# M051X.net
KiCad netlist of a schematic drawn in EAGLE
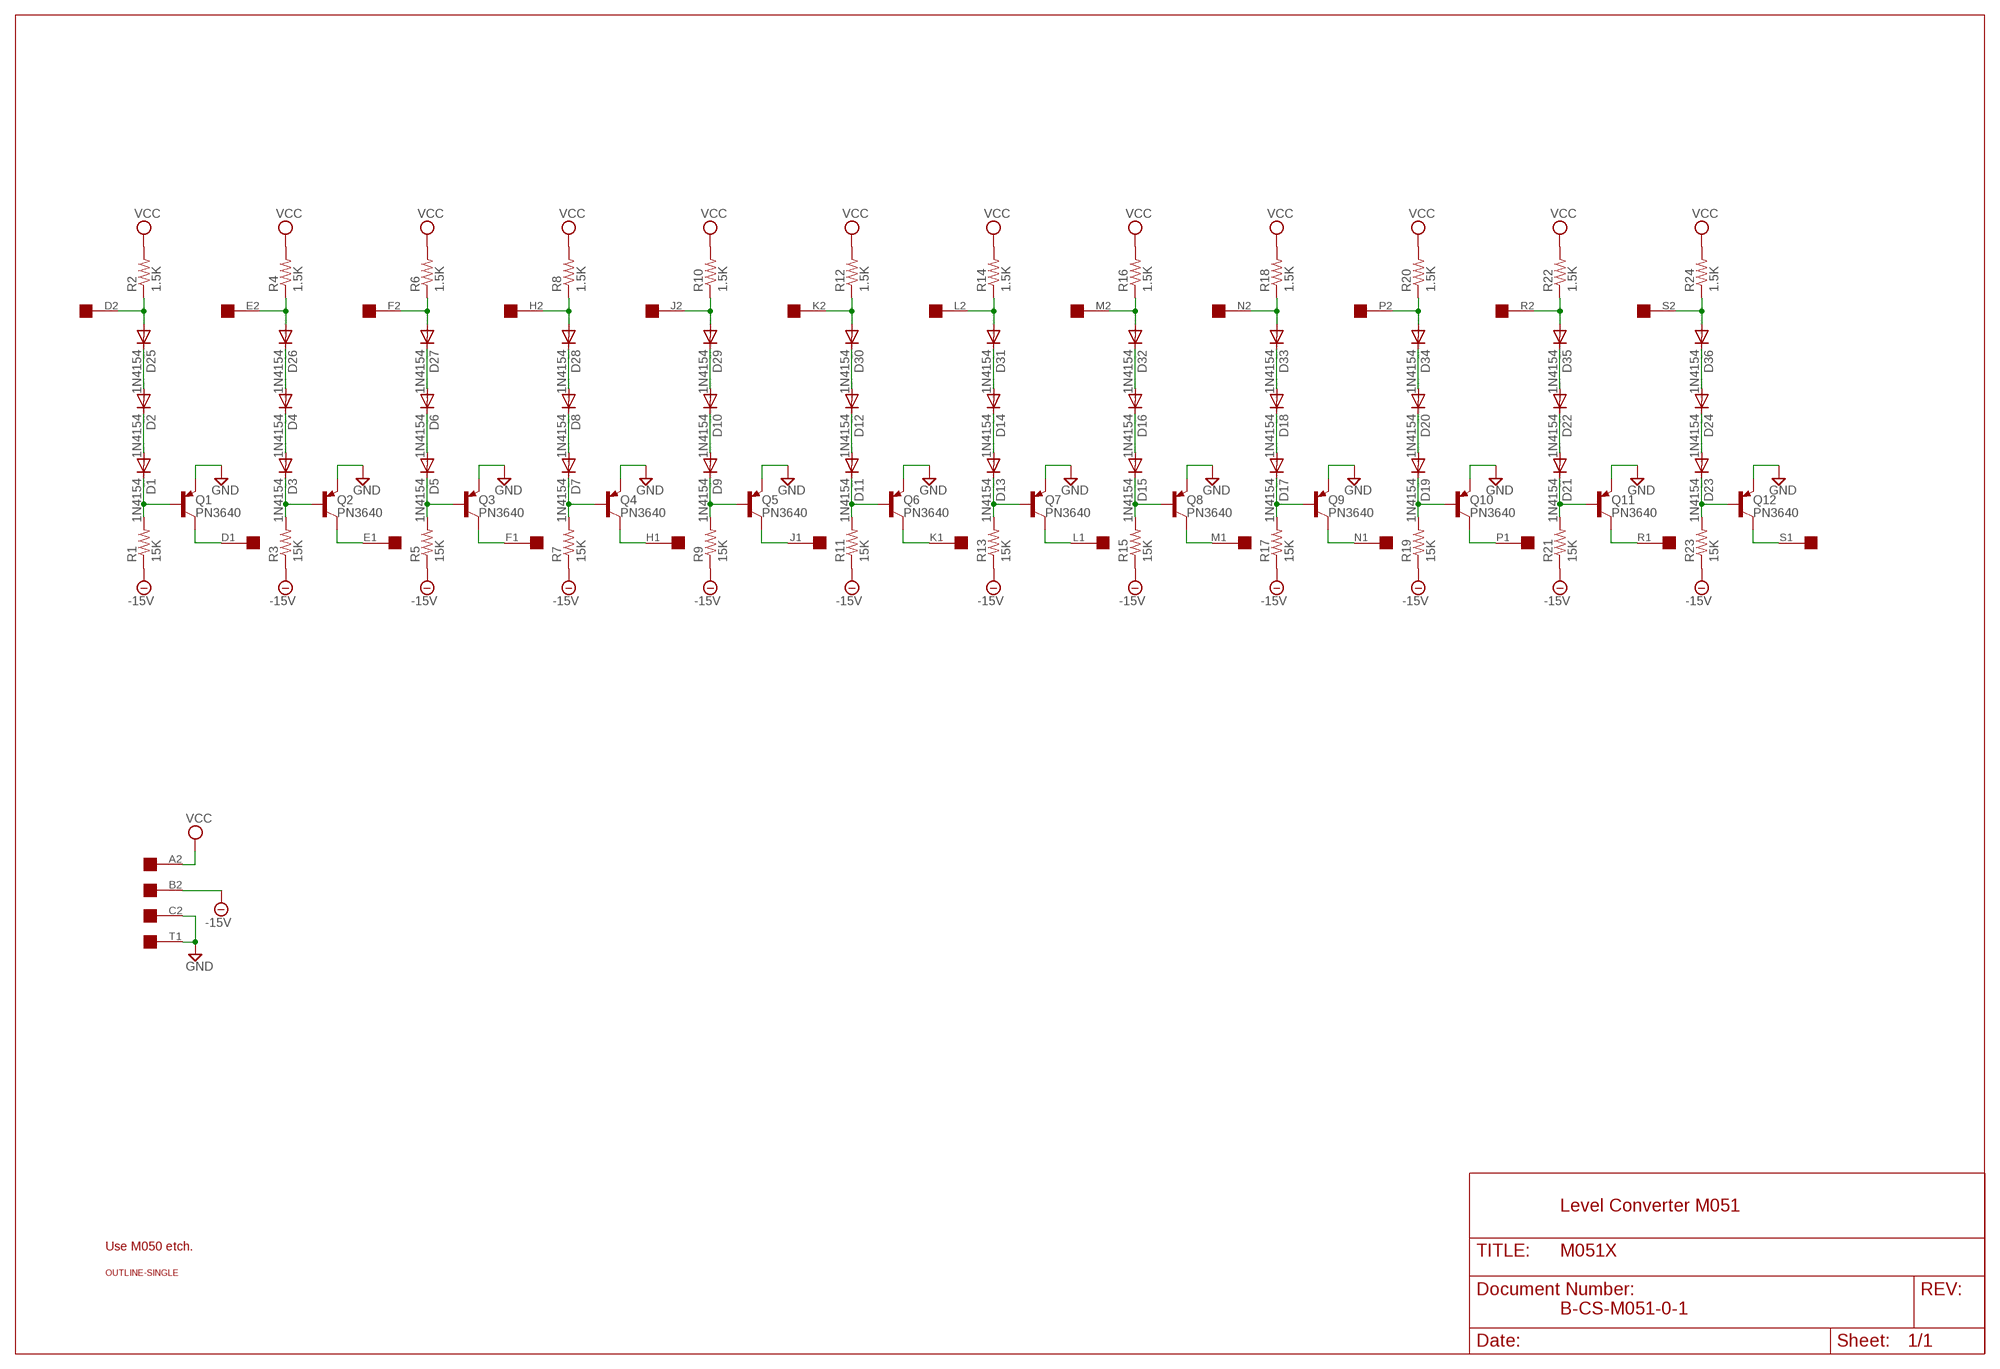
[diagram p0: schematic, sheet 1]

(export (version "E")
  (design (tool "Eeschema 10.0.6"))
  (components
    (comp (ref "D1")
      (value "1N4154")
      (footprint "eagle-import:DO35-10")
      (libsource (lib "eagle-import") (part "DIODE-DO35-10"))
    )
    (comp (ref "D2")
      (value "1N4154")
      (footprint "eagle-import:DO35-10")
      (libsource (lib "eagle-import") (part "DIODE-DO35-10"))
    )
    (comp (ref "D3")
      (value "1N4154")
      (footprint "eagle-import:DO35-10")
      (libsource (lib "eagle-import") (part "DIODE-DO35-10"))
    )
    (comp (ref "D4")
      (value "1N4154")
      (footprint "eagle-import:DO35-10")
      (libsource (lib "eagle-import") (part "DIODE-DO35-10"))
    )
    (comp (ref "D5")
      (value "1N4154")
      (footprint "eagle-import:DO35-10")
      (libsource (lib "eagle-import") (part "DIODE-DO35-10"))
    )
    (comp (ref "D6")
      (value "1N4154")
      (footprint "eagle-import:DO35-10")
      (libsource (lib "eagle-import") (part "DIODE-DO35-10"))
    )
    (comp (ref "D7")
      (value "1N4154")
      (footprint "eagle-import:DO35-10")
      (libsource (lib "eagle-import") (part "DIODE-DO35-10"))
    )
    (comp (ref "D8")
      (value "1N4154")
      (footprint "eagle-import:DO35-10")
      (libsource (lib "eagle-import") (part "DIODE-DO35-10"))
    )
    (comp (ref "D9")
      (value "1N4154")
      (footprint "eagle-import:DO35-10")
      (libsource (lib "eagle-import") (part "DIODE-DO35-10"))
    )
    (comp (ref "D10")
      (value "1N4154")
      (footprint "eagle-import:DO35-10")
      (libsource (lib "eagle-import") (part "DIODE-DO35-10"))
    )
    (comp (ref "D11")
      (value "1N4154")
      (footprint "eagle-import:DO35-10")
      (libsource (lib "eagle-import") (part "DIODE-DO35-10"))
    )
    (comp (ref "D12")
      (value "1N4154")
      (footprint "eagle-import:DO35-10")
      (libsource (lib "eagle-import") (part "DIODE-DO35-10"))
    )
    (comp (ref "D13")
      (value "1N4154")
      (footprint "eagle-import:DO35-10")
      (libsource (lib "eagle-import") (part "DIODE-DO35-10"))
    )
    (comp (ref "D14")
      (value "1N4154")
      (footprint "eagle-import:DO35-10")
      (libsource (lib "eagle-import") (part "DIODE-DO35-10"))
    )
    (comp (ref "D15")
      (value "1N4154")
      (footprint "eagle-import:DO35-10")
      (libsource (lib "eagle-import") (part "DIODE-DO35-10"))
    )
    (comp (ref "D16")
      (value "1N4154")
      (footprint "eagle-import:DO35-10")
      (libsource (lib "eagle-import") (part "DIODE-DO35-10"))
    )
    (comp (ref "D17")
      (value "1N4154")
      (footprint "eagle-import:DO35-10")
      (libsource (lib "eagle-import") (part "DIODE-DO35-10"))
    )
    (comp (ref "D18")
      (value "1N4154")
      (footprint "eagle-import:DO35-10")
      (libsource (lib "eagle-import") (part "DIODE-DO35-10"))
    )
    (comp (ref "D19")
      (value "1N4154")
      (footprint "eagle-import:DO35-10")
      (libsource (lib "eagle-import") (part "DIODE-DO35-10"))
    )
    (comp (ref "D20")
      (value "1N4154")
      (footprint "eagle-import:DO35-10")
      (libsource (lib "eagle-import") (part "DIODE-DO35-10"))
    )
    (comp (ref "D21")
      (value "1N4154")
      (footprint "eagle-import:DO35-10")
      (libsource (lib "eagle-import") (part "DIODE-DO35-10"))
    )
    (comp (ref "D22")
      (value "1N4154")
      (footprint "eagle-import:DO35-10")
      (libsource (lib "eagle-import") (part "DIODE-DO35-10"))
    )
    (comp (ref "D23")
      (value "1N4154")
      (footprint "eagle-import:DO35-10")
      (libsource (lib "eagle-import") (part "DIODE-DO35-10"))
    )
    (comp (ref "D24")
      (value "1N4154")
      (footprint "eagle-import:DO35-10")
      (libsource (lib "eagle-import") (part "DIODE-DO35-10"))
    )
    (comp (ref "D25")
      (value "1N4154")
      (footprint "eagle-import:DO35-10")
      (libsource (lib "eagle-import") (part "DIODE-DO35-10"))
    )
    (comp (ref "D26")
      (value "1N4154")
      (footprint "eagle-import:DO35-10")
      (libsource (lib "eagle-import") (part "DIODE-DO35-10"))
    )
    (comp (ref "D27")
      (value "1N4154")
      (footprint "eagle-import:DO35-10")
      (libsource (lib "eagle-import") (part "DIODE-DO35-10"))
    )
    (comp (ref "D28")
      (value "1N4154")
      (footprint "eagle-import:DO35-10")
      (libsource (lib "eagle-import") (part "DIODE-DO35-10"))
    )
    (comp (ref "D29")
      (value "1N4154")
      (footprint "eagle-import:DO35-10")
      (libsource (lib "eagle-import") (part "DIODE-DO35-10"))
    )
    (comp (ref "D30")
      (value "1N4154")
      (footprint "eagle-import:DO35-10")
      (libsource (lib "eagle-import") (part "DIODE-DO35-10"))
    )
    (comp (ref "D31")
      (value "1N4154")
      (footprint "eagle-import:DO35-10")
      (libsource (lib "eagle-import") (part "DIODE-DO35-10"))
    )
    (comp (ref "D32")
      (value "1N4154")
      (footprint "eagle-import:DO35-10")
      (libsource (lib "eagle-import") (part "DIODE-DO35-10"))
    )
    (comp (ref "D33")
      (value "1N4154")
      (footprint "eagle-import:DO35-10")
      (libsource (lib "eagle-import") (part "DIODE-DO35-10"))
    )
    (comp (ref "D34")
      (value "1N4154")
      (footprint "eagle-import:DO35-10")
      (libsource (lib "eagle-import") (part "DIODE-DO35-10"))
    )
    (comp (ref "D35")
      (value "1N4154")
      (footprint "eagle-import:DO35-10")
      (libsource (lib "eagle-import") (part "DIODE-DO35-10"))
    )
    (comp (ref "D36")
      (value "1N4154")
      (footprint "eagle-import:DO35-10")
      (libsource (lib "eagle-import") (part "DIODE-DO35-10"))
    )
    (comp (ref "Q1")
      (value "PN3640")
      (footprint "eagle-import:TO5")
      (libsource (lib "eagle-import") (part "-PNP-TO5"))
    )
    (comp (ref "Q2")
      (value "PN3640")
      (footprint "eagle-import:TO5")
      (libsource (lib "eagle-import") (part "-PNP-TO5"))
    )
    (comp (ref "Q3")
      (value "PN3640")
      (footprint "eagle-import:TO5")
      (libsource (lib "eagle-import") (part "-PNP-TO5"))
    )
    (comp (ref "Q4")
      (value "PN3640")
      (footprint "eagle-import:TO5")
      (libsource (lib "eagle-import") (part "-PNP-TO5"))
    )
    (comp (ref "Q5")
      (value "PN3640")
      (footprint "eagle-import:TO5")
      (libsource (lib "eagle-import") (part "-PNP-TO5"))
    )
    (comp (ref "Q6")
      (value "PN3640")
      (footprint "eagle-import:TO5")
      (libsource (lib "eagle-import") (part "-PNP-TO5"))
    )
    (comp (ref "Q7")
      (value "PN3640")
      (footprint "eagle-import:TO5")
      (libsource (lib "eagle-import") (part "-PNP-TO5"))
    )
    (comp (ref "Q8")
      (value "PN3640")
      (footprint "eagle-import:TO5")
      (libsource (lib "eagle-import") (part "-PNP-TO5"))
    )
    (comp (ref "Q9")
      (value "PN3640")
      (footprint "eagle-import:TO5")
      (libsource (lib "eagle-import") (part "-PNP-TO5"))
    )
    (comp (ref "Q10")
      (value "PN3640")
      (footprint "eagle-import:TO5")
      (libsource (lib "eagle-import") (part "-PNP-TO5"))
    )
    (comp (ref "Q11")
      (value "PN3640")
      (footprint "eagle-import:TO5")
      (libsource (lib "eagle-import") (part "-PNP-TO5"))
    )
    (comp (ref "Q12")
      (value "PN3640")
      (footprint "eagle-import:TO5")
      (libsource (lib "eagle-import") (part "-PNP-TO5"))
    )
    (comp (ref "R1")
      (value "15K")
      (footprint "eagle-import:0207_10")
      (libsource (lib "eagle-import") (part "R-US_0207/10"))
    )
    (comp (ref "R2")
      (value "1.5K")
      (footprint "eagle-import:0207_10")
      (libsource (lib "eagle-import") (part "R-US_0207/10"))
    )
    (comp (ref "R3")
      (value "15K")
      (footprint "eagle-import:0207_10")
      (libsource (lib "eagle-import") (part "R-US_0207/10"))
    )
    (comp (ref "R4")
      (value "1.5K")
      (footprint "eagle-import:0207_10")
      (libsource (lib "eagle-import") (part "R-US_0207/10"))
    )
    (comp (ref "R5")
      (value "15K")
      (footprint "eagle-import:0207_10")
      (libsource (lib "eagle-import") (part "R-US_0207/10"))
    )
    (comp (ref "R6")
      (value "1.5K")
      (footprint "eagle-import:0207_10")
      (libsource (lib "eagle-import") (part "R-US_0207/10"))
    )
    (comp (ref "R7")
      (value "15K")
      (footprint "eagle-import:0207_10")
      (libsource (lib "eagle-import") (part "R-US_0207/10"))
    )
    (comp (ref "R8")
      (value "1.5K")
      (footprint "eagle-import:0207_10")
      (libsource (lib "eagle-import") (part "R-US_0207/10"))
    )
    (comp (ref "R9")
      (value "15K")
      (footprint "eagle-import:0207_10")
      (libsource (lib "eagle-import") (part "R-US_0207/10"))
    )
    (comp (ref "R10")
      (value "1.5K")
      (footprint "eagle-import:0207_10")
      (libsource (lib "eagle-import") (part "R-US_0207/10"))
    )
    (comp (ref "R11")
      (value "15K")
      (footprint "eagle-import:0207_10")
      (libsource (lib "eagle-import") (part "R-US_0207/10"))
    )
    (comp (ref "R12")
      (value "1.5K")
      (footprint "eagle-import:0207_10")
      (libsource (lib "eagle-import") (part "R-US_0207/10"))
    )
    (comp (ref "R13")
      (value "15K")
      (footprint "eagle-import:0207_10")
      (libsource (lib "eagle-import") (part "R-US_0207/10"))
    )
    (comp (ref "R14")
      (value "1.5K")
      (footprint "eagle-import:0207_10")
      (libsource (lib "eagle-import") (part "R-US_0207/10"))
    )
    (comp (ref "R15")
      (value "15K")
      (footprint "eagle-import:0207_10")
      (libsource (lib "eagle-import") (part "R-US_0207/10"))
    )
    (comp (ref "R16")
      (value "1.5K")
      (footprint "eagle-import:0207_10")
      (libsource (lib "eagle-import") (part "R-US_0207/10"))
    )
    (comp (ref "R17")
      (value "15K")
      (footprint "eagle-import:0207_10")
      (libsource (lib "eagle-import") (part "R-US_0207/10"))
    )
    (comp (ref "R18")
      (value "1.5K")
      (footprint "eagle-import:0207_10")
      (libsource (lib "eagle-import") (part "R-US_0207/10"))
    )
    (comp (ref "R19")
      (value "15K")
      (footprint "eagle-import:0207_10")
      (libsource (lib "eagle-import") (part "R-US_0207/10"))
    )
    (comp (ref "R20")
      (value "1.5K")
      (footprint "eagle-import:0207_10")
      (libsource (lib "eagle-import") (part "R-US_0207/10"))
    )
    (comp (ref "R21")
      (value "15K")
      (footprint "eagle-import:0207_10")
      (libsource (lib "eagle-import") (part "R-US_0207/10"))
    )
    (comp (ref "R22")
      (value "1.5K")
      (footprint "eagle-import:0207_10")
      (libsource (lib "eagle-import") (part "R-US_0207/10"))
    )
    (comp (ref "R23")
      (value "15K")
      (footprint "eagle-import:0207_10")
      (libsource (lib "eagle-import") (part "R-US_0207/10"))
    )
    (comp (ref "R24")
      (value "1.5K")
      (footprint "eagle-import:0207_10")
      (libsource (lib "eagle-import") (part "R-US_0207/10"))
    )
    (comp (ref "U$1")
      (value "OUTLINE-SINGLE")
      (footprint "eagle-import:SINGLE")
      (libsource (lib "eagle-import") (part "OUTLINE-SINGLE"))
    )
    (comp (ref "U$2")
      (value "SINGLE")
      (footprint "eagle-import:EDGE-CON2")
      (libsource (lib "eagle-import") (part "SINGLE"))
    )
  )
  (nets
    (net (code "1") (name "-15V") (class "Default")
      (node (ref "R1") (pin "1") (pinfunction "1_1") (pintype "passive"))
      (node (ref "R11") (pin "1") (pinfunction "1_1") (pintype "passive"))
      (node (ref "R13") (pin "1") (pinfunction "1_1") (pintype "passive"))
      (node (ref "R15") (pin "1") (pinfunction "1_1") (pintype "passive"))
      (node (ref "R17") (pin "1") (pinfunction "1_1") (pintype "passive"))
      (node (ref "R19") (pin "1") (pinfunction "1_1") (pintype "passive"))
      (node (ref "R21") (pin "1") (pinfunction "1_1") (pintype "passive"))
      (node (ref "R23") (pin "1") (pinfunction "1_1") (pintype "passive"))
      (node (ref "R3") (pin "1") (pinfunction "1_1") (pintype "passive"))
      (node (ref "R5") (pin "1") (pinfunction "1_1") (pintype "passive"))
      (node (ref "R7") (pin "1") (pinfunction "1_1") (pintype "passive"))
      (node (ref "R9") (pin "1") (pinfunction "1_1") (pintype "passive"))
      (node (ref "U$2") (pin "B2") (pinfunction "1_B2") (pintype "bidirectional"))
    )
    (net (code "2") (name "GND") (class "Default")
      (node (ref "Q1") (pin "1") (pinfunction "E_1") (pintype "passive"))
      (node (ref "Q10") (pin "1") (pinfunction "E_1") (pintype "passive"))
      (node (ref "Q11") (pin "1") (pinfunction "E_1") (pintype "passive"))
      (node (ref "Q12") (pin "1") (pinfunction "E_1") (pintype "passive"))
      (node (ref "Q2") (pin "1") (pinfunction "E_1") (pintype "passive"))
      (node (ref "Q3") (pin "1") (pinfunction "E_1") (pintype "passive"))
      (node (ref "Q4") (pin "1") (pinfunction "E_1") (pintype "passive"))
      (node (ref "Q5") (pin "1") (pinfunction "E_1") (pintype "passive"))
      (node (ref "Q6") (pin "1") (pinfunction "E_1") (pintype "passive"))
      (node (ref "Q7") (pin "1") (pinfunction "E_1") (pintype "passive"))
      (node (ref "Q8") (pin "1") (pinfunction "E_1") (pintype "passive"))
      (node (ref "Q9") (pin "1") (pinfunction "E_1") (pintype "passive"))
      (node (ref "U$2") (pin "C2") (pinfunction "1_C2") (pintype "bidirectional"))
      (node (ref "U$2") (pin "T1") (pinfunction "1_T1") (pintype "bidirectional"))
    )
    (net (code "3") (name "Net-(D1-PadA)") (class "Default")
      (node (ref "D1") (pin "A") (pinfunction "A_A") (pintype "passive"))
      (node (ref "D2") (pin "C") (pinfunction "C_C") (pintype "passive"))
    )
    (net (code "4") (name "Net-(D2-PadA)") (class "Default")
      (node (ref "D2") (pin "A") (pinfunction "A_A") (pintype "passive"))
      (node (ref "D25") (pin "C") (pinfunction "C_C") (pintype "passive"))
    )
    (net (code "5") (name "Net-(D3-PadA)") (class "Default")
      (node (ref "D3") (pin "A") (pinfunction "A_A") (pintype "passive"))
      (node (ref "D4") (pin "C") (pinfunction "C_C") (pintype "passive"))
    )
    (net (code "6") (name "Net-(D5-PadA)") (class "Default")
      (node (ref "D5") (pin "A") (pinfunction "A_A") (pintype "passive"))
      (node (ref "D6") (pin "C") (pinfunction "C_C") (pintype "passive"))
    )
    (net (code "7") (name "Net-(D7-PadA)") (class "Default")
      (node (ref "D7") (pin "A") (pinfunction "A_A") (pintype "passive"))
      (node (ref "D8") (pin "C") (pinfunction "C_C") (pintype "passive"))
    )
    (net (code "8") (name "Net-(D10-PadA)") (class "Default")
      (node (ref "D10") (pin "A") (pinfunction "A_A") (pintype "passive"))
      (node (ref "D29") (pin "C") (pinfunction "C_C") (pintype "passive"))
    )
    (net (code "9") (name "Net-(D10-PadC)") (class "Default")
      (node (ref "D10") (pin "C") (pinfunction "C_C") (pintype "passive"))
      (node (ref "D9") (pin "A") (pinfunction "A_A") (pintype "passive"))
    )
    (net (code "10") (name "Net-(D11-PadA)") (class "Default")
      (node (ref "D11") (pin "A") (pinfunction "A_A") (pintype "passive"))
      (node (ref "D12") (pin "C") (pinfunction "C_C") (pintype "passive"))
    )
    (net (code "11") (name "Net-(D12-PadA)") (class "Default")
      (node (ref "D12") (pin "A") (pinfunction "A_A") (pintype "passive"))
      (node (ref "D30") (pin "C") (pinfunction "C_C") (pintype "passive"))
    )
    (net (code "12") (name "Net-(D13-PadA)") (class "Default")
      (node (ref "D13") (pin "A") (pinfunction "A_A") (pintype "passive"))
      (node (ref "D14") (pin "C") (pinfunction "C_C") (pintype "passive"))
    )
    (net (code "13") (name "Net-(D14-PadA)") (class "Default")
      (node (ref "D14") (pin "A") (pinfunction "A_A") (pintype "passive"))
      (node (ref "D31") (pin "C") (pinfunction "C_C") (pintype "passive"))
    )
    (net (code "14") (name "Net-(D15-PadA)") (class "Default")
      (node (ref "D15") (pin "A") (pinfunction "A_A") (pintype "passive"))
      (node (ref "D16") (pin "C") (pinfunction "C_C") (pintype "passive"))
    )
    (net (code "15") (name "Net-(D16-PadA)") (class "Default")
      (node (ref "D16") (pin "A") (pinfunction "A_A") (pintype "passive"))
      (node (ref "D32") (pin "C") (pinfunction "C_C") (pintype "passive"))
    )
    (net (code "16") (name "Net-(D17-PadA)") (class "Default")
      (node (ref "D17") (pin "A") (pinfunction "A_A") (pintype "passive"))
      (node (ref "D18") (pin "C") (pinfunction "C_C") (pintype "passive"))
    )
    (net (code "17") (name "Net-(D18-PadA)") (class "Default")
      (node (ref "D18") (pin "A") (pinfunction "A_A") (pintype "passive"))
      (node (ref "D33") (pin "C") (pinfunction "C_C") (pintype "passive"))
    )
    (net (code "18") (name "Net-(D19-PadA)") (class "Default")
      (node (ref "D19") (pin "A") (pinfunction "A_A") (pintype "passive"))
      (node (ref "D20") (pin "C") (pinfunction "C_C") (pintype "passive"))
    )
    (net (code "19") (name "Net-(D20-PadA)") (class "Default")
      (node (ref "D20") (pin "A") (pinfunction "A_A") (pintype "passive"))
      (node (ref "D34") (pin "C") (pinfunction "C_C") (pintype "passive"))
    )
    (net (code "20") (name "Net-(D21-PadA)") (class "Default")
      (node (ref "D21") (pin "A") (pinfunction "A_A") (pintype "passive"))
      (node (ref "D22") (pin "C") (pinfunction "C_C") (pintype "passive"))
    )
    (net (code "21") (name "Net-(D22-PadA)") (class "Default")
      (node (ref "D22") (pin "A") (pinfunction "A_A") (pintype "passive"))
      (node (ref "D35") (pin "C") (pinfunction "C_C") (pintype "passive"))
    )
    (net (code "22") (name "Net-(D23-PadA)") (class "Default")
      (node (ref "D23") (pin "A") (pinfunction "A_A") (pintype "passive"))
      (node (ref "D24") (pin "C") (pinfunction "C_C") (pintype "passive"))
    )
    (net (code "23") (name "Net-(D24-PadA)") (class "Default")
      (node (ref "D24") (pin "A") (pinfunction "A_A") (pintype "passive"))
      (node (ref "D36") (pin "C") (pinfunction "C_C") (pintype "passive"))
    )
    (net (code "24") (name "Net-(D26-PadC)") (class "Default")
      (node (ref "D26") (pin "C") (pinfunction "C_C") (pintype "passive"))
      (node (ref "D4") (pin "A") (pinfunction "A_A") (pintype "passive"))
    )
    (net (code "25") (name "Net-(D27-PadC)") (class "Default")
      (node (ref "D27") (pin "C") (pinfunction "C_C") (pintype "passive"))
      (node (ref "D6") (pin "A") (pinfunction "A_A") (pintype "passive"))
    )
    (net (code "26") (name "Net-(D28-PadC)") (class "Default")
      (node (ref "D28") (pin "C") (pinfunction "C_C") (pintype "passive"))
      (node (ref "D8") (pin "A") (pinfunction "A_A") (pintype "passive"))
    )
    (net (code "27") (name "Net-(Q1-B)") (class "Default")
      (node (ref "D1") (pin "C") (pinfunction "C_C") (pintype "passive"))
      (node (ref "Q1") (pin "2") (pinfunction "B_2") (pintype "passive"))
      (node (ref "R1") (pin "2") (pinfunction "2_2") (pintype "passive"))
    )
    (net (code "28") (name "Net-(Q1-C)") (class "Default")
      (node (ref "Q1") (pin "3") (pinfunction "C_3") (pintype "passive"))
      (node (ref "U$2") (pin "D1") (pinfunction "1_D1") (pintype "bidirectional"))
    )
    (net (code "29") (name "Net-(Q2-B)") (class "Default")
      (node (ref "D3") (pin "C") (pinfunction "C_C") (pintype "passive"))
      (node (ref "Q2") (pin "2") (pinfunction "B_2") (pintype "passive"))
      (node (ref "R3") (pin "2") (pinfunction "2_2") (pintype "passive"))
    )
    (net (code "30") (name "Net-(Q2-C)") (class "Default")
      (node (ref "Q2") (pin "3") (pinfunction "C_3") (pintype "passive"))
      (node (ref "U$2") (pin "E1") (pinfunction "1_E1") (pintype "bidirectional"))
    )
    (net (code "31") (name "Net-(Q3-B)") (class "Default")
      (node (ref "D5") (pin "C") (pinfunction "C_C") (pintype "passive"))
      (node (ref "Q3") (pin "2") (pinfunction "B_2") (pintype "passive"))
      (node (ref "R5") (pin "2") (pinfunction "2_2") (pintype "passive"))
    )
    (net (code "32") (name "Net-(Q3-C)") (class "Default")
      (node (ref "Q3") (pin "3") (pinfunction "C_3") (pintype "passive"))
      (node (ref "U$2") (pin "F1") (pinfunction "1_F1") (pintype "bidirectional"))
    )
    (net (code "33") (name "Net-(Q4-B)") (class "Default")
      (node (ref "D7") (pin "C") (pinfunction "C_C") (pintype "passive"))
      (node (ref "Q4") (pin "2") (pinfunction "B_2") (pintype "passive"))
      (node (ref "R7") (pin "2") (pinfunction "2_2") (pintype "passive"))
    )
    (net (code "34") (name "Net-(Q4-C)") (class "Default")
      (node (ref "Q4") (pin "3") (pinfunction "C_3") (pintype "passive"))
      (node (ref "U$2") (pin "H1") (pinfunction "1_H1") (pintype "bidirectional"))
    )
    (net (code "35") (name "Net-(Q5-B)") (class "Default")
      (node (ref "D9") (pin "C") (pinfunction "C_C") (pintype "passive"))
      (node (ref "Q5") (pin "2") (pinfunction "B_2") (pintype "passive"))
      (node (ref "R9") (pin "2") (pinfunction "2_2") (pintype "passive"))
    )
    (net (code "36") (name "Net-(Q5-C)") (class "Default")
      (node (ref "Q5") (pin "3") (pinfunction "C_3") (pintype "passive"))
      (node (ref "U$2") (pin "J1") (pinfunction "1_J1") (pintype "bidirectional"))
    )
    (net (code "37") (name "Net-(Q6-B)") (class "Default")
      (node (ref "D11") (pin "C") (pinfunction "C_C") (pintype "passive"))
      (node (ref "Q6") (pin "2") (pinfunction "B_2") (pintype "passive"))
      (node (ref "R11") (pin "2") (pinfunction "2_2") (pintype "passive"))
    )
    (net (code "38") (name "Net-(Q6-C)") (class "Default")
      (node (ref "Q6") (pin "3") (pinfunction "C_3") (pintype "passive"))
      (node (ref "U$2") (pin "K1") (pinfunction "1_K1") (pintype "bidirectional"))
    )
    (net (code "39") (name "Net-(Q7-B)") (class "Default")
      (node (ref "D13") (pin "C") (pinfunction "C_C") (pintype "passive"))
      (node (ref "Q7") (pin "2") (pinfunction "B_2") (pintype "passive"))
      (node (ref "R13") (pin "2") (pinfunction "2_2") (pintype "passive"))
    )
    (net (code "40") (name "Net-(Q7-C)") (class "Default")
      (node (ref "Q7") (pin "3") (pinfunction "C_3") (pintype "passive"))
      (node (ref "U$2") (pin "L1") (pinfunction "1_L1") (pintype "bidirectional"))
    )
    (net (code "41") (name "Net-(Q8-B)") (class "Default")
      (node (ref "D15") (pin "C") (pinfunction "C_C") (pintype "passive"))
      (node (ref "Q8") (pin "2") (pinfunction "B_2") (pintype "passive"))
      (node (ref "R15") (pin "2") (pinfunction "2_2") (pintype "passive"))
    )
    (net (code "42") (name "Net-(Q8-C)") (class "Default")
      (node (ref "Q8") (pin "3") (pinfunction "C_3") (pintype "passive"))
      (node (ref "U$2") (pin "M1") (pinfunction "1_M1") (pintype "bidirectional"))
    )
    (net (code "43") (name "Net-(Q9-B)") (class "Default")
      (node (ref "D17") (pin "C") (pinfunction "C_C") (pintype "passive"))
      (node (ref "Q9") (pin "2") (pinfunction "B_2") (pintype "passive"))
      (node (ref "R17") (pin "2") (pinfunction "2_2") (pintype "passive"))
    )
    (net (code "44") (name "Net-(Q9-C)") (class "Default")
      (node (ref "Q9") (pin "3") (pinfunction "C_3") (pintype "passive"))
      (node (ref "U$2") (pin "N1") (pinfunction "1_N1") (pintype "bidirectional"))
    )
    (net (code "45") (name "Net-(Q10-B)") (class "Default")
      (node (ref "D19") (pin "C") (pinfunction "C_C") (pintype "passive"))
      (node (ref "Q10") (pin "2") (pinfunction "B_2") (pintype "passive"))
      (node (ref "R19") (pin "2") (pinfunction "2_2") (pintype "passive"))
    )
    (net (code "46") (name "Net-(Q10-C)") (class "Default")
      (node (ref "Q10") (pin "3") (pinfunction "C_3") (pintype "passive"))
      (node (ref "U$2") (pin "P1") (pinfunction "1_P1") (pintype "bidirectional"))
    )
    (net (code "47") (name "Net-(Q11-B)") (class "Default")
      (node (ref "D21") (pin "C") (pinfunction "C_C") (pintype "passive"))
      (node (ref "Q11") (pin "2") (pinfunction "B_2") (pintype "passive"))
      (node (ref "R21") (pin "2") (pinfunction "2_2") (pintype "passive"))
    )
    (net (code "48") (name "Net-(Q11-C)") (class "Default")
      (node (ref "Q11") (pin "3") (pinfunction "C_3") (pintype "passive"))
      (node (ref "U$2") (pin "R1") (pinfunction "1_R1") (pintype "bidirectional"))
    )
    (net (code "49") (name "Net-(Q12-B)") (class "Default")
      (node (ref "D23") (pin "C") (pinfunction "C_C") (pintype "passive"))
      (node (ref "Q12") (pin "2") (pinfunction "B_2") (pintype "passive"))
      (node (ref "R23") (pin "2") (pinfunction "2_2") (pintype "passive"))
    )
    (net (code "50") (name "Net-(Q12-C)") (class "Default")
      (node (ref "Q12") (pin "3") (pinfunction "C_3") (pintype "passive"))
      (node (ref "U$2") (pin "S1") (pinfunction "1_S1") (pintype "bidirectional"))
    )
    (net (code "51") (name "Net-(U$2AB-1)") (class "Default")
      (node (ref "D35") (pin "A") (pinfunction "A_A") (pintype "passive"))
      (node (ref "R22") (pin "1") (pinfunction "1_1") (pintype "passive"))
      (node (ref "U$2") (pin "R2") (pinfunction "1_R2") (pintype "bidirectional"))
    )
    (net (code "52") (name "Net-(U$2AD-1)") (class "Default")
      (node (ref "D36") (pin "A") (pinfunction "A_A") (pintype "passive"))
      (node (ref "R24") (pin "1") (pinfunction "1_1") (pintype "passive"))
      (node (ref "U$2") (pin "S2") (pinfunction "1_S2") (pintype "bidirectional"))
    )
    (net (code "53") (name "Net-(U$2H-1)") (class "Default")
      (node (ref "D25") (pin "A") (pinfunction "A_A") (pintype "passive"))
      (node (ref "R2") (pin "1") (pinfunction "1_1") (pintype "passive"))
      (node (ref "U$2") (pin "D2") (pinfunction "1_D2") (pintype "bidirectional"))
    )
    (net (code "54") (name "Net-(U$2J-1)") (class "Default")
      (node (ref "D26") (pin "A") (pinfunction "A_A") (pintype "passive"))
      (node (ref "R4") (pin "1") (pinfunction "1_1") (pintype "passive"))
      (node (ref "U$2") (pin "E2") (pinfunction "1_E2") (pintype "bidirectional"))
    )
    (net (code "55") (name "Net-(U$2L-1)") (class "Default")
      (node (ref "D27") (pin "A") (pinfunction "A_A") (pintype "passive"))
      (node (ref "R6") (pin "1") (pinfunction "1_1") (pintype "passive"))
      (node (ref "U$2") (pin "F2") (pinfunction "1_F2") (pintype "bidirectional"))
    )
    (net (code "56") (name "Net-(U$2N-1)") (class "Default")
      (node (ref "D28") (pin "A") (pinfunction "A_A") (pintype "passive"))
      (node (ref "R8") (pin "1") (pinfunction "1_1") (pintype "passive"))
      (node (ref "U$2") (pin "H2") (pinfunction "1_H2") (pintype "bidirectional"))
    )
    (net (code "57") (name "Net-(U$2P-1)") (class "Default")
      (node (ref "D29") (pin "A") (pinfunction "A_A") (pintype "passive"))
      (node (ref "R10") (pin "1") (pinfunction "1_1") (pintype "passive"))
      (node (ref "U$2") (pin "J2") (pinfunction "1_J2") (pintype "bidirectional"))
    )
    (net (code "58") (name "Net-(U$2R-1)") (class "Default")
      (node (ref "D30") (pin "A") (pinfunction "A_A") (pintype "passive"))
      (node (ref "R12") (pin "1") (pinfunction "1_1") (pintype "passive"))
      (node (ref "U$2") (pin "K2") (pinfunction "1_K2") (pintype "bidirectional"))
    )
    (net (code "59") (name "Net-(U$2T-1)") (class "Default")
      (node (ref "D31") (pin "A") (pinfunction "A_A") (pintype "passive"))
      (node (ref "R14") (pin "1") (pinfunction "1_1") (pintype "passive"))
      (node (ref "U$2") (pin "L2") (pinfunction "1_L2") (pintype "bidirectional"))
    )
    (net (code "60") (name "Net-(U$2V-1)") (class "Default")
      (node (ref "D32") (pin "A") (pinfunction "A_A") (pintype "passive"))
      (node (ref "R16") (pin "1") (pinfunction "1_1") (pintype "passive"))
      (node (ref "U$2") (pin "M2") (pinfunction "1_M2") (pintype "bidirectional"))
    )
    (net (code "61") (name "Net-(U$2X-1)") (class "Default")
      (node (ref "D33") (pin "A") (pinfunction "A_A") (pintype "passive"))
      (node (ref "R18") (pin "1") (pinfunction "1_1") (pintype "passive"))
      (node (ref "U$2") (pin "N2") (pinfunction "1_N2") (pintype "bidirectional"))
    )
    (net (code "62") (name "Net-(U$2Z-1)") (class "Default")
      (node (ref "D34") (pin "A") (pinfunction "A_A") (pintype "passive"))
      (node (ref "R20") (pin "1") (pinfunction "1_1") (pintype "passive"))
      (node (ref "U$2") (pin "P2") (pinfunction "1_P2") (pintype "bidirectional"))
    )
    (net (code "63") (name "VCC") (class "Default")
      (node (ref "R10") (pin "2") (pinfunction "2_2") (pintype "passive"))
      (node (ref "R12") (pin "2") (pinfunction "2_2") (pintype "passive"))
      (node (ref "R14") (pin "2") (pinfunction "2_2") (pintype "passive"))
      (node (ref "R16") (pin "2") (pinfunction "2_2") (pintype "passive"))
      (node (ref "R18") (pin "2") (pinfunction "2_2") (pintype "passive"))
      (node (ref "R2") (pin "2") (pinfunction "2_2") (pintype "passive"))
      (node (ref "R20") (pin "2") (pinfunction "2_2") (pintype "passive"))
      (node (ref "R22") (pin "2") (pinfunction "2_2") (pintype "passive"))
      (node (ref "R24") (pin "2") (pinfunction "2_2") (pintype "passive"))
      (node (ref "R4") (pin "2") (pinfunction "2_2") (pintype "passive"))
      (node (ref "R6") (pin "2") (pinfunction "2_2") (pintype "passive"))
      (node (ref "R8") (pin "2") (pinfunction "2_2") (pintype "passive"))
      (node (ref "U$2") (pin "A2") (pinfunction "1_A2") (pintype "bidirectional"))
    )
  )
)
